# BT_AQ_DOL_R2.net
KiCad netlist of a schematic drawn in EAGLE
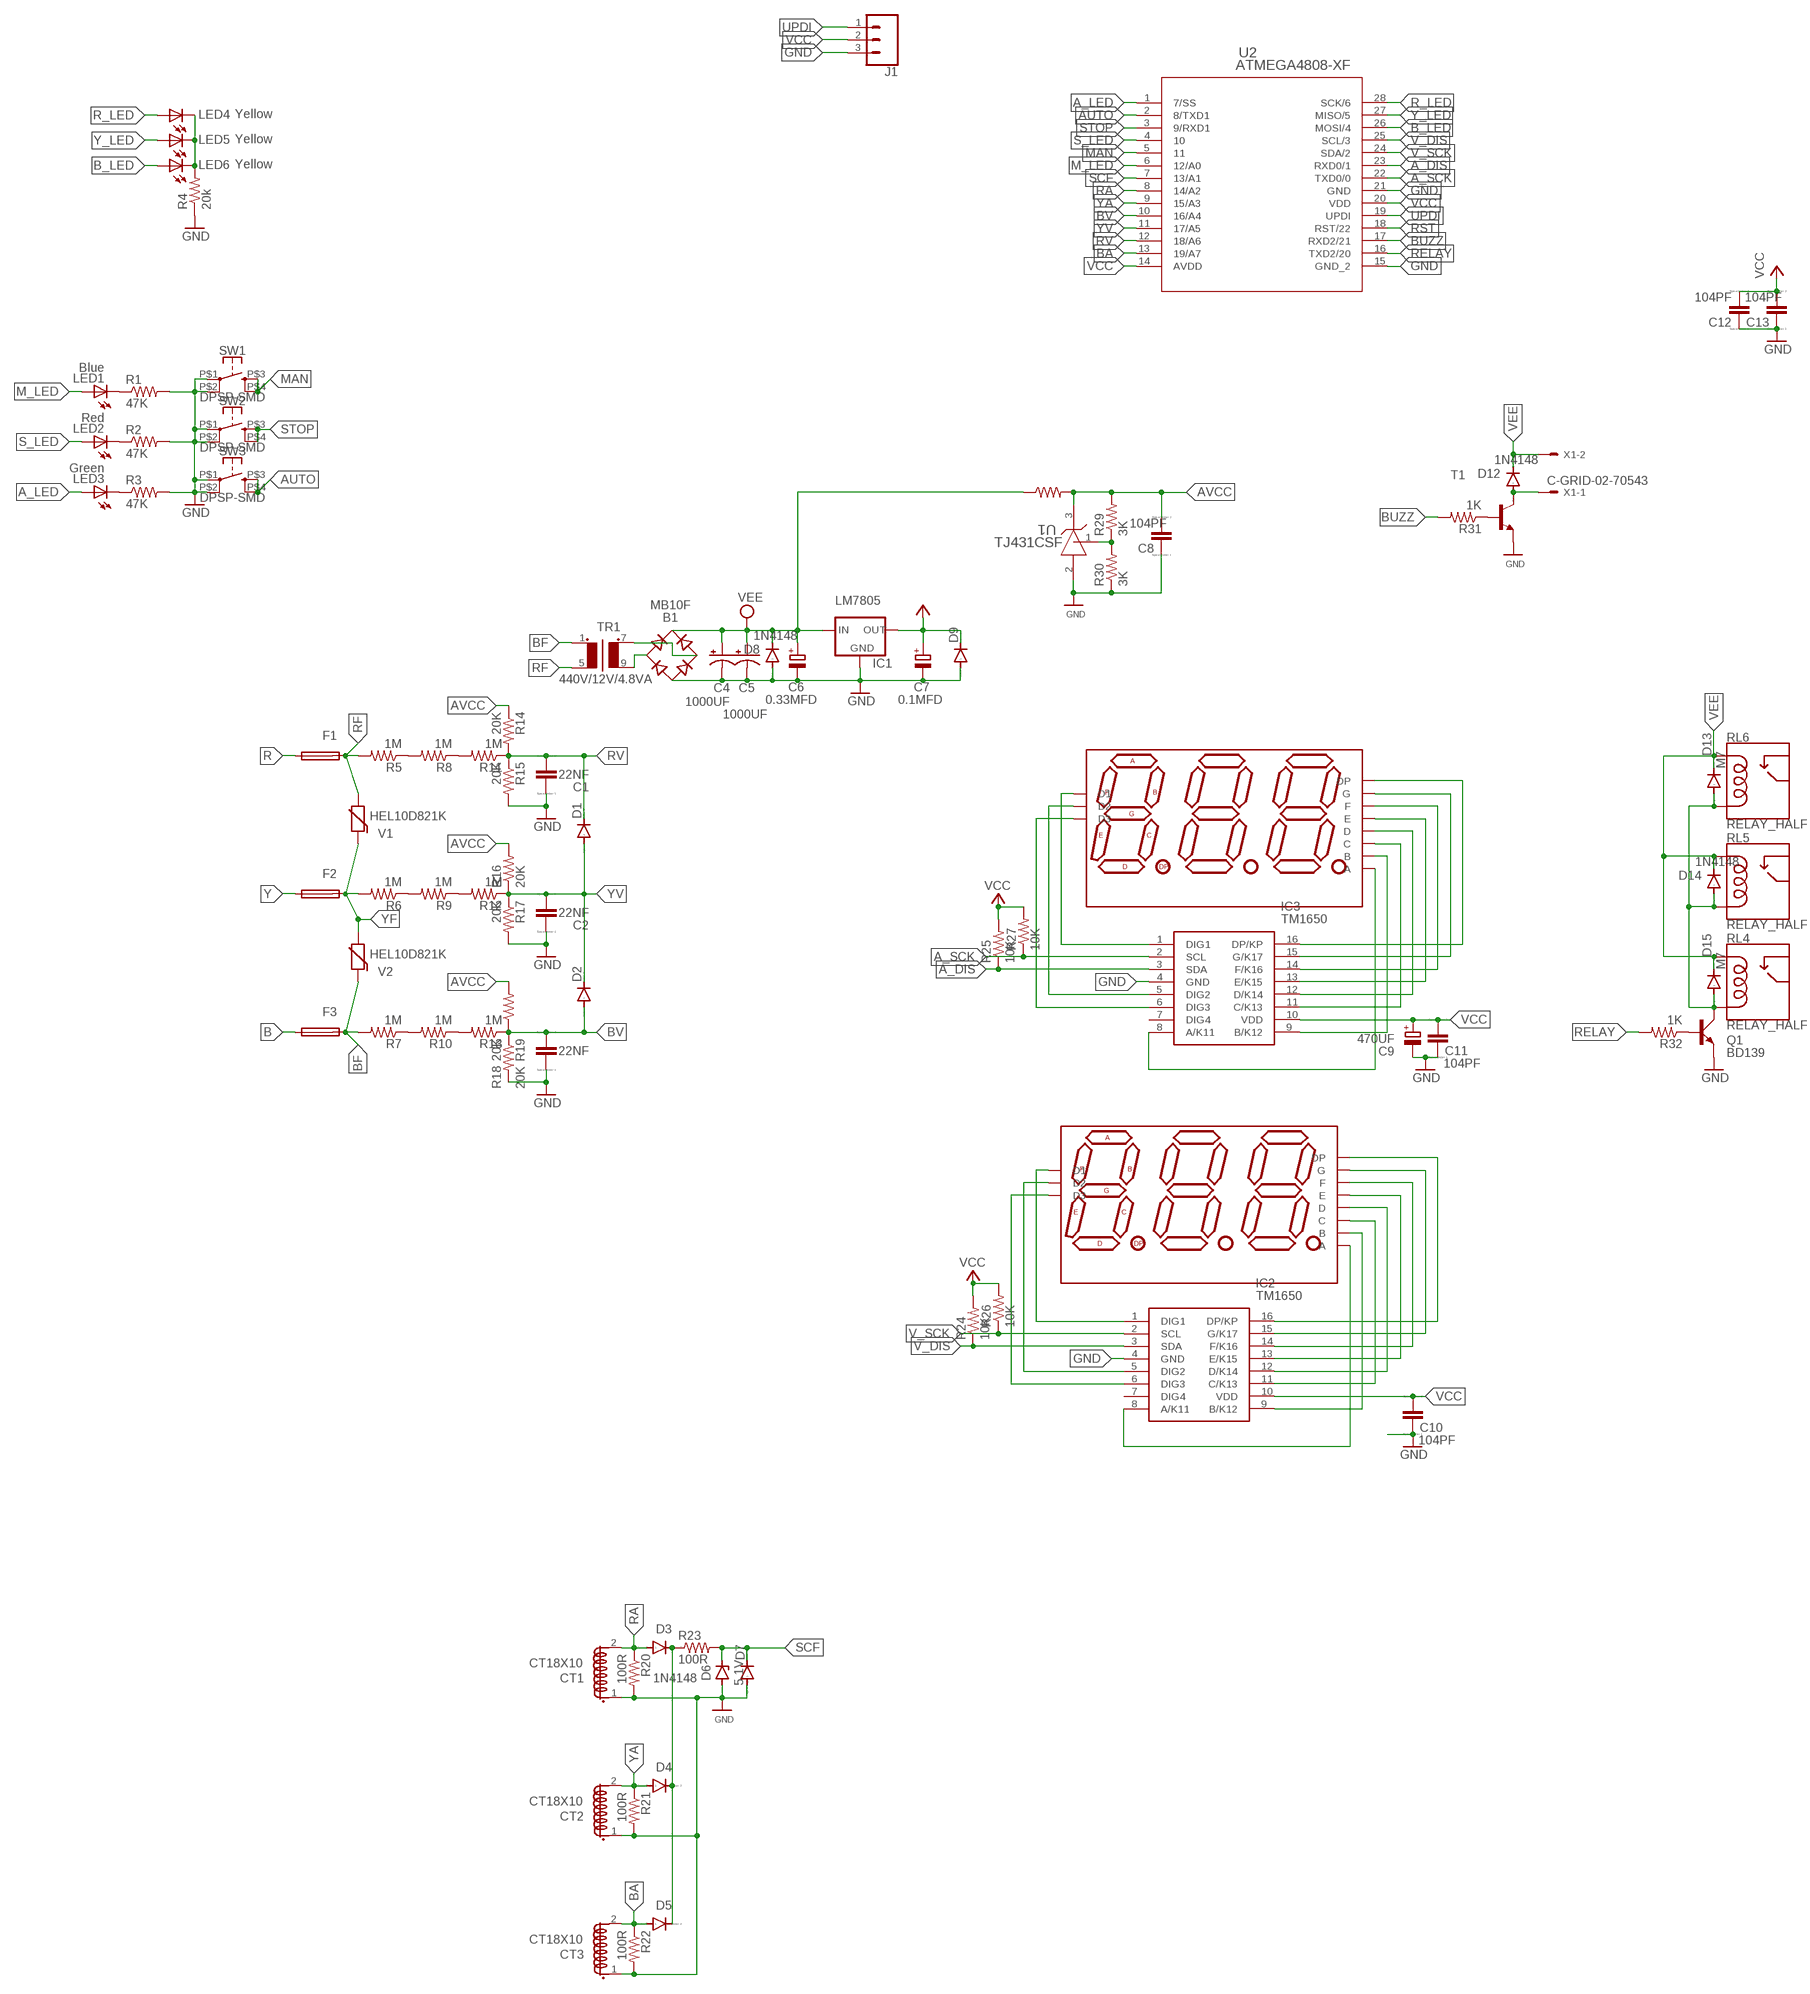
[diagram p0: schematic, sheet 1]

(export (version "E")
  (design (tool "Eeschema 10.0.6"))
  (components
    (comp (ref "B1")
      (value "MB10F")
      (footprint "eagle-import:SOIC-4")
      (libsource (lib "eagle-import") (part "MBS8"))
    )
    (comp (ref "C1")
      (value "22NF")
      (footprint "eagle-import:C1206")
      (libsource (lib "eagle-import") (part "CC1206"))
    )
    (comp (ref "C2")
      (value "22NF")
      (footprint "eagle-import:C1206")
      (libsource (lib "eagle-import") (part "CC1206"))
    )
    (comp (ref "C3")
      (value "22NF")
      (footprint "eagle-import:C1206")
      (libsource (lib "eagle-import") (part "CC1206"))
    )
    (comp (ref "C4")
      (value "1000UF")
      (footprint "eagle-import:E3,5-10")
      (libsource (lib "eagle-import") (part "CPOL-USE3.5-10"))
    )
    (comp (ref "C5")
      (value "1000UF")
      (footprint "eagle-import:E3,5-10")
      (libsource (lib "eagle-import") (part "CPOL-USE3.5-10"))
    )
    (comp (ref "C6")
      (value "0.33MFD")
      (footprint "eagle-import:E2,5-5")
      (libsource (lib "eagle-import") (part "CPOL-EUE2.5-5"))
    )
    (comp (ref "C7")
      (value "0.1MFD")
      (footprint "eagle-import:E2,5-5")
      (libsource (lib "eagle-import") (part "CPOL-EUE2.5-5"))
    )
    (comp (ref "C8")
      (value "104PF")
      (footprint "eagle-import:C1206")
      (libsource (lib "eagle-import") (part "CC1206"))
    )
    (comp (ref "C9")
      (value "470UF")
      (footprint "eagle-import:E3,5-8")
      (libsource (lib "eagle-import") (part "CPOL-EUE3.5-8"))
    )
    (comp (ref "C10")
      (value "104PF")
      (footprint "eagle-import:C1206")
      (libsource (lib "eagle-import") (part "CC1206"))
    )
    (comp (ref "C11")
      (value "104PF")
      (footprint "eagle-import:C1206")
      (libsource (lib "eagle-import") (part "CC1206"))
    )
    (comp (ref "C12")
      (value "104PF")
      (footprint "eagle-import:C1206")
      (libsource (lib "eagle-import") (part "CC1206"))
    )
    (comp (ref "C13")
      (value "104PF")
      (footprint "eagle-import:C1206")
      (libsource (lib "eagle-import") (part "CC1206"))
    )
    (comp (ref "CT1")
      (value "CT18X10")
      (footprint "eagle-import:ZMCT103C")
      (libsource (lib "eagle-import") (part "CT18X10"))
    )
    (comp (ref "CT2")
      (value "CT18X10")
      (footprint "eagle-import:ZMCT103C")
      (libsource (lib "eagle-import") (part "CT18X10"))
    )
    (comp (ref "CT3")
      (value "CT18X10")
      (footprint "eagle-import:ZMCT103C")
      (libsource (lib "eagle-import") (part "CT18X10"))
    )
    (comp (ref "D1")
      (value "DIODE-DO214AA")
      (footprint "eagle-import:DO214AA")
      (libsource (lib "eagle-import") (part "DIODE-DO214AA"))
    )
    (comp (ref "D2")
      (value "DIODE-DO214AA")
      (footprint "eagle-import:DO214AA")
      (libsource (lib "eagle-import") (part "DIODE-DO214AA"))
    )
    (comp (ref "D3")
      (value "1N4148")
      (footprint "eagle-import:MINIMELF")
      (libsource (lib "eagle-import") (part "DIODE-MINIMELF"))
    )
    (comp (ref "D4")
      (value "1N4148")
      (footprint "eagle-import:MINIMELF")
      (libsource (lib "eagle-import") (part "DIODE-MINIMELF"))
    )
    (comp (ref "D5")
      (value "1N4148")
      (footprint "eagle-import:MINIMELF")
      (libsource (lib "eagle-import") (part "DIODE-MINIMELF"))
    )
    (comp (ref "D6")
      (value "5.1V")
      (footprint "eagle-import:DIOMELF3516")
      (libsource (lib "eagle-import") (part "ZENER_DO-213AA(SOD-80)_"))
    )
    (comp (ref "D7")
      (value "DIODE-DO214AA")
      (footprint "eagle-import:DO214AA")
      (libsource (lib "eagle-import") (part "DIODE-DO214AA"))
    )
    (comp (ref "D8")
      (value "1N4148")
      (footprint "eagle-import:MINIMELF")
      (libsource (lib "eagle-import") (part "DIODE-MINIMELF"))
    )
    (comp (ref "D9")
      (value "DIODE-DO214AA")
      (footprint "eagle-import:DO214AA")
      (libsource (lib "eagle-import") (part "DIODE-DO214AA"))
    )
    (comp (ref "D10")
      (value "SUNR036CC3D")
      (footprint "eagle-import:7S3D036_DIP")
      (libsource (lib "eagle-import") (part "7SEGMENT-3DIGITDIP"))
    )
    (comp (ref "D11")
      (value "SUNR036CC3D")
      (footprint "eagle-import:7S3D036_DIP")
      (libsource (lib "eagle-import") (part "7SEGMENT-3DIGITDIP"))
    )
    (comp (ref "D12")
      (value "1N4148")
      (footprint "eagle-import:MINIMELF")
      (libsource (lib "eagle-import") (part "DIODE-MINIMELF"))
    )
    (comp (ref "D13")
      (value "M7")
      (footprint "eagle-import:DO-214AC")
      (libsource (lib "eagle-import") (part "DIODE-DO-214AC"))
    )
    (comp (ref "D14")
      (value "1N4148")
      (footprint "eagle-import:MINIMELF")
      (libsource (lib "eagle-import") (part "DIODE-MINIMELF"))
    )
    (comp (ref "D15")
      (value "M7")
      (footprint "eagle-import:DO-214AC")
      (libsource (lib "eagle-import") (part "DIODE-DO-214AC"))
    )
    (comp (ref "F1")
      (value "TRF600-150")
      (footprint "eagle-import:TRF600-150")
      (libsource (lib "eagle-import") (part "PPTCPTH"))
    )
    (comp (ref "F2")
      (value "TRF600-150")
      (footprint "eagle-import:TRF600-150")
      (libsource (lib "eagle-import") (part "PPTCPTH"))
    )
    (comp (ref "F3")
      (value "TRF600-150")
      (footprint "eagle-import:TRF600-150")
      (libsource (lib "eagle-import") (part "PPTCPTH"))
    )
    (comp (ref "IC1")
      (value "LM7805")
      (footprint "eagle-import:78XXS")
      (libsource (lib "eagle-import") (part "78XXS"))
    )
    (comp (ref "IC2")
      (value "TM1650")
      (footprint "eagle-import:SOIC127P604X185-16N")
      (fields (field (name "MANUFACTURER_PART_NUMBER") "tm1650"))
      (libsource (lib "eagle-import") (part "TM1650"))
    )
    (comp (ref "IC3")
      (value "TM1650")
      (footprint "eagle-import:SOIC127P604X185-16N")
      (fields (field (name "MANUFACTURER_PART_NUMBER") "tm1650"))
      (libsource (lib "eagle-import") (part "TM1650"))
    )
    (comp (ref "J1")
      (value "CONN_03")
      (footprint "eagle-import:1X03")
      (libsource (lib "eagle-import") (part "CONN_03"))
    )
    (comp (ref "LED1")
      (value "Blue")
      (footprint "eagle-import:LED3MM")
      (libsource (lib "eagle-import") (part "LED3MM"))
    )
    (comp (ref "LED2")
      (value "Red")
      (footprint "eagle-import:LED3MM")
      (libsource (lib "eagle-import") (part "LED3MM"))
    )
    (comp (ref "LED3")
      (value "Green")
      (footprint "eagle-import:LED3MM")
      (libsource (lib "eagle-import") (part "LED3MM"))
    )
    (comp (ref "LED4")
      (value "Yellow")
      (footprint "eagle-import:LED3MM")
      (libsource (lib "eagle-import") (part "LED3MM"))
    )
    (comp (ref "LED5")
      (value "Yellow")
      (footprint "eagle-import:LED3MM")
      (libsource (lib "eagle-import") (part "LED3MM"))
    )
    (comp (ref "LED6")
      (value "Yellow")
      (footprint "eagle-import:LED3MM")
      (libsource (lib "eagle-import") (part "LED3MM"))
    )
    (comp (ref "Q1")
      (value "BD139")
      (footprint "eagle-import:TO126AV")
      (libsource (lib "eagle-import") (part "BD139"))
    )
    (comp (ref "R1")
      (value "47K")
      (footprint "eagle-import:M1206")
      (libsource (lib "eagle-import") (part "rcl_334_R-US_M1206"))
    )
    (comp (ref "R2")
      (value "47K")
      (footprint "eagle-import:M1206")
      (libsource (lib "eagle-import") (part "rcl_334_R-US_M1206"))
    )
    (comp (ref "R3")
      (value "47K")
      (footprint "eagle-import:M1206")
      (libsource (lib "eagle-import") (part "rcl_334_R-US_M1206"))
    )
    (comp (ref "R4")
      (value "20k")
      (footprint "eagle-import:M1206")
      (libsource (lib "eagle-import") (part "rcl_334_R-US_M1206"))
    )
    (comp (ref "R5")
      (value "1M")
      (footprint "eagle-import:M1206")
      (libsource (lib "eagle-import") (part "rcl_334_R-US_M1206"))
    )
    (comp (ref "R6")
      (value "1M")
      (footprint "eagle-import:M1206")
      (libsource (lib "eagle-import") (part "rcl_334_R-US_M1206"))
    )
    (comp (ref "R7")
      (value "1M")
      (footprint "eagle-import:M1206")
      (libsource (lib "eagle-import") (part "rcl_334_R-US_M1206"))
    )
    (comp (ref "R8")
      (value "1M")
      (footprint "eagle-import:M1206")
      (libsource (lib "eagle-import") (part "rcl_334_R-US_M1206"))
    )
    (comp (ref "R9")
      (value "1M")
      (footprint "eagle-import:M1206")
      (libsource (lib "eagle-import") (part "rcl_334_R-US_M1206"))
    )
    (comp (ref "R10")
      (value "1M")
      (footprint "eagle-import:M1206")
      (libsource (lib "eagle-import") (part "rcl_334_R-US_M1206"))
    )
    (comp (ref "R11")
      (value "1M")
      (footprint "eagle-import:M1206")
      (libsource (lib "eagle-import") (part "rcl_334_R-US_M1206"))
    )
    (comp (ref "R12")
      (value "1M")
      (footprint "eagle-import:M1206")
      (libsource (lib "eagle-import") (part "rcl_334_R-US_M1206"))
    )
    (comp (ref "R13")
      (value "1M")
      (footprint "eagle-import:M1206")
      (libsource (lib "eagle-import") (part "rcl_334_R-US_M1206"))
    )
    (comp (ref "R14")
      (value "20K")
      (footprint "eagle-import:M1206")
      (libsource (lib "eagle-import") (part "rcl_334_R-US_M1206"))
    )
    (comp (ref "R15")
      (value "20K")
      (footprint "eagle-import:M1206")
      (libsource (lib "eagle-import") (part "rcl_334_R-US_M1206"))
    )
    (comp (ref "R16")
      (value "20K")
      (footprint "eagle-import:M1206")
      (libsource (lib "eagle-import") (part "rcl_334_R-US_M1206"))
    )
    (comp (ref "R17")
      (value "20K")
      (footprint "eagle-import:M1206")
      (libsource (lib "eagle-import") (part "rcl_334_R-US_M1206"))
    )
    (comp (ref "R18")
      (value "20K")
      (footprint "eagle-import:M1206")
      (libsource (lib "eagle-import") (part "rcl_334_R-US_M1206"))
    )
    (comp (ref "R19")
      (value "20K")
      (footprint "eagle-import:M1206")
      (libsource (lib "eagle-import") (part "rcl_334_R-US_M1206"))
    )
    (comp (ref "R20")
      (value "100R")
      (footprint "eagle-import:M1206")
      (libsource (lib "eagle-import") (part "R-US_M1206"))
    )
    (comp (ref "R21")
      (value "100R")
      (footprint "eagle-import:M1206")
      (libsource (lib "eagle-import") (part "R-US_M1206"))
    )
    (comp (ref "R22")
      (value "100R")
      (footprint "eagle-import:M1206")
      (libsource (lib "eagle-import") (part "R-US_M1206"))
    )
    (comp (ref "R23")
      (value "100R")
      (footprint "eagle-import:M1206")
      (libsource (lib "eagle-import") (part "R-US_M1206"))
    )
    (comp (ref "R24")
      (value "10K")
      (footprint "eagle-import:M1206")
      (libsource (lib "eagle-import") (part "rcl_334_R-US_M1206"))
    )
    (comp (ref "R25")
      (value "10K")
      (footprint "eagle-import:M1206")
      (libsource (lib "eagle-import") (part "rcl_334_R-US_M1206"))
    )
    (comp (ref "R26")
      (value "10K")
      (footprint "eagle-import:M1206")
      (libsource (lib "eagle-import") (part "rcl_334_R-US_M1206"))
    )
    (comp (ref "R27")
      (value "10K")
      (footprint "eagle-import:M1206")
      (libsource (lib "eagle-import") (part "rcl_334_R-US_M1206"))
    )
    (comp (ref "R28")
      (value "10K")
      (footprint "eagle-import:M1206")
      (libsource (lib "eagle-import") (part "R-US_M1206"))
    )
    (comp (ref "R29")
      (value "3K")
      (footprint "eagle-import:M1206")
      (libsource (lib "eagle-import") (part "R-US_M1206"))
    )
    (comp (ref "R30")
      (value "3K")
      (footprint "eagle-import:M1206")
      (libsource (lib "eagle-import") (part "R-US_M1206"))
    )
    (comp (ref "R31")
      (value "1K")
      (footprint "eagle-import:M1206")
      (libsource (lib "eagle-import") (part "rcl_334_R-US_M1206"))
    )
    (comp (ref "R32")
      (value "1K")
      (footprint "eagle-import:M1206")
      (libsource (lib "eagle-import") (part "rcl_334_R-US_M1206"))
    )
    (comp (ref "RL4")
      (value "RELAY_HALF")
      (footprint "eagle-import:DT90_HALF")
      (libsource (lib "eagle-import") (part "RELAY_HALF"))
    )
    (comp (ref "RL5")
      (value "RELAY_HALF")
      (footprint "eagle-import:DT90_HALF")
      (libsource (lib "eagle-import") (part "RELAY_HALF"))
    )
    (comp (ref "RL6")
      (value "RELAY_HALF")
      (footprint "eagle-import:DT90_HALF")
      (libsource (lib "eagle-import") (part "RELAY_HALF"))
    )
    (comp (ref "SW1")
      (value "DPSP-SMD")
      (footprint "eagle-import:B3F-40XX-ROUND-SMD")
      (libsource (lib "eagle-import") (part "DPSP-SMD"))
    )
    (comp (ref "SW2")
      (value "DPSP-SMD")
      (footprint "eagle-import:B3F-40XX-ROUND-SMD")
      (libsource (lib "eagle-import") (part "DPSP-SMD"))
    )
    (comp (ref "SW3")
      (value "DPSP-SMD")
      (footprint "eagle-import:B3F-40XX-ROUND-SMD")
      (libsource (lib "eagle-import") (part "DPSP-SMD"))
    )
    (comp (ref "T1")
      (value "MMUN2213LT1-NPN-SC59-BEC")
      (footprint "eagle-import:SC59-BEC")
      (libsource (lib "eagle-import") (part "-NPN-SC59-BECMMUN2213LT1"))
    )
    (comp (ref "TR1")
      (value "440V/12V/4.8VA")
      (footprint "eagle-import:440V12V6VA")
      (libsource (lib "eagle-import") (part "TRANSFORMER6VA"))
    )
    (comp (ref "U1")
      (value "TJ431CSF")
      (footprint "eagle-import:SOT-23")
      (fields
        (field (name "MANUFACTURER_PART_NUMBER") "TL431IDBZTG4")
        (field (name "COPYRIGHT") "Copyright (C) 2022 Ultra Librarian. All rights reserved.")
      )
      (libsource (lib "eagle-import") (part "TJ431CSFDBZ0003A_L"))
    )
    (comp (ref "U2")
      (value "ATMEGA4808-XF")
      (footprint "eagle-import:SSOP28_SS_MCH")
      (fields (field (name "COPYRIGHT") "Copyright (C) 2022 Ultra Librarian. All rights reserved."))
      (libsource (lib "eagle-import") (part "ATMEGA4808-XF"))
    )
    (comp (ref "V1")
      (value "HEL10D821K")
      (footprint "eagle-import:10MM")
      (libsource (lib "eagle-import") (part "VARISTOR"))
    )
    (comp (ref "V2")
      (value "HEL10D821K")
      (footprint "eagle-import:10MM")
      (libsource (lib "eagle-import") (part "VARISTOR"))
    )
    (comp (ref "X1")
      (value "C-GRID-02-70543")
      (footprint "eagle-import:70543-02")
      (fields (field (name "MF") "MOLEX"))
      (libsource (lib "eagle-import") (part "C-GRID-02-70543"))
    )
  )
  (nets
    (net (code "1") (name "AUTO") (class "Default")
      (node (ref "SW3") (pin "P$3") (pinfunction "3_P$3") (pintype "passive"))
      (node (ref "SW3") (pin "P$4") (pinfunction "4_P$4") (pintype "passive"))
      (node (ref "U2") (pin "2") (pinfunction "8/TXD1_2") (pintype "bidirectional"))
    )
    (net (code "2") (name "AVCC") (class "Default")
      (node (ref "C8") (pin "2") (pinfunction "2_2") (pintype "passive"))
      (node (ref "R14") (pin "1") (pinfunction "1_1") (pintype "passive"))
      (node (ref "R16") (pin "2") (pinfunction "2_2") (pintype "passive"))
      (node (ref "R18") (pin "2") (pinfunction "2_2") (pintype "passive"))
      (node (ref "R28") (pin "2") (pinfunction "2_2") (pintype "passive"))
      (node (ref "R29") (pin "2") (pinfunction "2_2") (pintype "passive"))
      (node (ref "U1") (pin "3") (pinfunction "CATHODE_3") (pintype "passive"))
    )
    (net (code "3") (name "A_DIS") (class "Default")
      (node (ref "IC3") (pin "3") (pinfunction "SDA_3") (pintype "input"))
      (node (ref "R25") (pin "1") (pinfunction "1_1") (pintype "passive"))
      (node (ref "U2") (pin "23") (pinfunction "RXD0/1_23") (pintype "bidirectional"))
    )
    (net (code "4") (name "A_LED") (class "Default")
      (node (ref "LED3") (pin "A") (pinfunction "A_A") (pintype "passive"))
      (node (ref "U2") (pin "1") (pinfunction "7/SS_1") (pintype "bidirectional"))
    )
    (net (code "5") (name "A_SCK") (class "Default")
      (node (ref "IC3") (pin "2") (pinfunction "SCL_2") (pintype "input"))
      (node (ref "R27") (pin "1") (pinfunction "1_1") (pintype "passive"))
      (node (ref "U2") (pin "22") (pinfunction "TXD0/0_22") (pintype "bidirectional"))
    )
    (net (code "6") (name "B") (class "Default")
      (node (ref "F3") (pin "1") (pinfunction "1_1") (pintype "passive"))
    )
    (net (code "7") (name "BA") (class "Default")
      (node (ref "CT3") (pin "2") (pinfunction "S1.2_2") (pintype "passive"))
      (node (ref "D5") (pin "A") (pinfunction "A_A") (pintype "passive"))
      (node (ref "R22") (pin "1") (pinfunction "1_1") (pintype "passive"))
      (node (ref "U2") (pin "13") (pinfunction "19/A7_13") (pintype "bidirectional"))
    )
    (net (code "8") (name "BF") (class "Default")
      (node (ref "F3") (pin "2") (pinfunction "2_2") (pintype "passive"))
      (node (ref "R7") (pin "2") (pinfunction "2_2") (pintype "passive"))
      (node (ref "TR1") (pin "1") (pinfunction "P1_1") (pintype "passive"))
      (node (ref "V2") (pin "1") (pinfunction "1_1") (pintype "passive"))
    )
    (net (code "9") (name "BUZZ") (class "Default")
      (node (ref "R31") (pin "2") (pinfunction "2_2") (pintype "passive"))
      (node (ref "U2") (pin "17") (pinfunction "RXD2/21_17") (pintype "bidirectional"))
    )
    (net (code "10") (name "BV") (class "Default")
      (node (ref "C3") (pin "2") (pinfunction "2_2") (pintype "passive"))
      (node (ref "D2") (pin "A") (pinfunction "A_A") (pintype "passive"))
      (node (ref "R13") (pin "1") (pinfunction "1_1") (pintype "passive"))
      (node (ref "R18") (pin "1") (pinfunction "1_1") (pintype "passive"))
      (node (ref "R19") (pin "1") (pinfunction "1_1") (pintype "passive"))
      (node (ref "U2") (pin "10") (pinfunction "16/A4_10") (pintype "bidirectional"))
    )
    (net (code "11") (name "B_LED") (class "Default")
      (node (ref "LED6") (pin "A") (pinfunction "A_A") (pintype "passive"))
      (node (ref "U2") (pin "26") (pinfunction "MOSI/4_26") (pintype "bidirectional"))
    )
    (net (code "12") (name "GND") (class "Default")
      (node (ref "B1") (pin "-") (pinfunction "-_-") (pintype "passive"))
      (node (ref "C1") (pin "1") (pinfunction "1_1") (pintype "passive"))
      (node (ref "C10") (pin "1") (pinfunction "1_1") (pintype "passive"))
      (node (ref "C11") (pin "1") (pinfunction "1_1") (pintype "passive"))
      (node (ref "C12") (pin "1") (pinfunction "1_1") (pintype "passive"))
      (node (ref "C13") (pin "1") (pinfunction "1_1") (pintype "passive"))
      (node (ref "C2") (pin "1") (pinfunction "1_1") (pintype "passive"))
      (node (ref "C3") (pin "1") (pinfunction "1_1") (pintype "passive"))
      (node (ref "C4") (pin "-") (pinfunction "-_-") (pintype "passive"))
      (node (ref "C5") (pin "-") (pinfunction "-_-") (pintype "passive"))
      (node (ref "C6") (pin "-") (pinfunction "-_-") (pintype "passive"))
      (node (ref "C7") (pin "-") (pinfunction "-_-") (pintype "passive"))
      (node (ref "C8") (pin "1") (pinfunction "1_1") (pintype "passive"))
      (node (ref "C9") (pin "-") (pinfunction "-_-") (pintype "passive"))
      (node (ref "CT1") (pin "1") (pinfunction "S1.1_1") (pintype "passive"))
      (node (ref "CT2") (pin "1") (pinfunction "S1.1_1") (pintype "passive"))
      (node (ref "CT3") (pin "1") (pinfunction "S1.1_1") (pintype "passive"))
      (node (ref "D6") (pin "2") (pinfunction "A_2") (pintype "passive"))
      (node (ref "D7") (pin "A") (pinfunction "A_A") (pintype "passive"))
      (node (ref "D8") (pin "A") (pinfunction "A_A") (pintype "passive"))
      (node (ref "D9") (pin "A") (pinfunction "A_A") (pintype "passive"))
      (node (ref "IC1") (pin "GND") (pinfunction "GND_GND") (pintype "input"))
      (node (ref "IC2") (pin "4") (pinfunction "GND_4") (pintype "power_in"))
      (node (ref "IC3") (pin "4") (pinfunction "GND_4") (pintype "power_in"))
      (node (ref "J1") (pin "3") (pinfunction "3_3") (pintype "passive"))
      (node (ref "Q1") (pin "E") (pinfunction "E_E") (pintype "passive"))
      (node (ref "R1") (pin "2") (pinfunction "2_2") (pintype "passive"))
      (node (ref "R15") (pin "2") (pinfunction "2_2") (pintype "passive"))
      (node (ref "R17") (pin "2") (pinfunction "2_2") (pintype "passive"))
      (node (ref "R19") (pin "2") (pinfunction "2_2") (pintype "passive"))
      (node (ref "R2") (pin "2") (pinfunction "2_2") (pintype "passive"))
      (node (ref "R20") (pin "2") (pinfunction "2_2") (pintype "passive"))
      (node (ref "R21") (pin "2") (pinfunction "2_2") (pintype "passive"))
      (node (ref "R22") (pin "2") (pinfunction "2_2") (pintype "passive"))
      (node (ref "R3") (pin "2") (pinfunction "2_2") (pintype "passive"))
      (node (ref "R30") (pin "1") (pinfunction "1_1") (pintype "passive"))
      (node (ref "R4") (pin "1") (pinfunction "1_1") (pintype "passive"))
      (node (ref "SW1") (pin "P$1") (pinfunction "1_P$1") (pintype "passive"))
      (node (ref "SW1") (pin "P$2") (pinfunction "2_P$2") (pintype "passive"))
      (node (ref "SW2") (pin "P$1") (pinfunction "1_P$1") (pintype "passive"))
      (node (ref "SW2") (pin "P$2") (pinfunction "2_P$2") (pintype "passive"))
      (node (ref "SW3") (pin "P$1") (pinfunction "1_P$1") (pintype "passive"))
      (node (ref "SW3") (pin "P$2") (pinfunction "2_P$2") (pintype "passive"))
      (node (ref "T1") (pin "E") (pinfunction "E_E") (pintype "passive"))
      (node (ref "U1") (pin "2") (pinfunction "ANODE_2") (pintype "passive"))
      (node (ref "U2") (pin "15") (pinfunction "GND_2_15") (pintype "passive"))
      (node (ref "U2") (pin "21") (pinfunction "GND_21") (pintype "passive"))
    )
    (net (code "13") (name "MAN") (class "Default")
      (node (ref "SW1") (pin "P$3") (pinfunction "3_P$3") (pintype "passive"))
      (node (ref "SW1") (pin "P$4") (pinfunction "4_P$4") (pintype "passive"))
      (node (ref "U2") (pin "5") (pinfunction "11_5") (pintype "bidirectional"))
    )
    (net (code "14") (name "M_LED") (class "Default")
      (node (ref "LED1") (pin "A") (pinfunction "A_A") (pintype "passive"))
      (node (ref "U2") (pin "6") (pinfunction "12/A0_6") (pintype "bidirectional"))
    )
    (net (code "15") (name "Net-(B1-AC1)") (class "Default")
      (node (ref "B1") (pin "~1") (pinfunction "AC1_~1") (pintype "passive"))
      (node (ref "TR1") (pin "9") (pinfunction "S2_9") (pintype "passive"))
    )
    (net (code "16") (name "Net-(B1-AC2)") (class "Default")
      (node (ref "B1") (pin "~2") (pinfunction "AC2_~2") (pintype "passive"))
      (node (ref "TR1") (pin "7") (pinfunction "S1_7") (pintype "passive"))
    )
    (net (code "17") (name "Net-(D3-PadC)") (class "Default")
      (node (ref "D3") (pin "C") (pinfunction "C_C") (pintype "passive"))
      (node (ref "D4") (pin "C") (pinfunction "C_C") (pintype "passive"))
      (node (ref "D5") (pin "C") (pinfunction "C_C") (pintype "passive"))
      (node (ref "R23") (pin "1") (pinfunction "1_1") (pintype "passive"))
    )
    (net (code "18") (name "Net-(D10-A)") (class "Default")
      (node (ref "D10") (pin "11") (pinfunction "A_11") (pintype "bidirectional"))
      (node (ref "IC2") (pin "8") (pinfunction "A/K11_8") (pintype "bidirectional"))
    )
    (net (code "19") (name "Net-(D10-B)") (class "Default")
      (node (ref "D10") (pin "7") (pinfunction "B_7") (pintype "bidirectional"))
      (node (ref "IC2") (pin "9") (pinfunction "B/K12_9") (pintype "bidirectional"))
    )
    (net (code "20") (name "Net-(D10-C)") (class "Default")
      (node (ref "D10") (pin "4") (pinfunction "C_4") (pintype "bidirectional"))
      (node (ref "IC2") (pin "11") (pinfunction "C/K13_11") (pintype "bidirectional"))
    )
    (net (code "21") (name "Net-(D10-D)") (class "Default")
      (node (ref "D10") (pin "2") (pinfunction "D_2") (pintype "bidirectional"))
      (node (ref "IC2") (pin "12") (pinfunction "D/K14_12") (pintype "bidirectional"))
    )
    (net (code "22") (name "Net-(D10-D1)") (class "Default")
      (node (ref "D10") (pin "12") (pinfunction "D1_12") (pintype "bidirectional"))
      (node (ref "IC2") (pin "1") (pinfunction "DIG1_1") (pintype "bidirectional"))
    )
    (net (code "23") (name "Net-(D10-D2)") (class "Default")
      (node (ref "D10") (pin "9") (pinfunction "D2_9") (pintype "bidirectional"))
      (node (ref "IC2") (pin "5") (pinfunction "DIG2_5") (pintype "bidirectional"))
    )
    (net (code "24") (name "Net-(D10-D3)") (class "Default")
      (node (ref "D10") (pin "8") (pinfunction "D3_8") (pintype "bidirectional"))
      (node (ref "IC2") (pin "6") (pinfunction "DIG3_6") (pintype "bidirectional"))
    )
    (net (code "25") (name "Net-(D10-DP)") (class "Default")
      (node (ref "D10") (pin "3") (pinfunction "DP_3") (pintype "bidirectional"))
      (node (ref "IC2") (pin "16") (pinfunction "DP/KP_16") (pintype "bidirectional"))
    )
    (net (code "26") (name "Net-(D10-E)") (class "Default")
      (node (ref "D10") (pin "1") (pinfunction "E_1") (pintype "bidirectional"))
      (node (ref "IC2") (pin "13") (pinfunction "E/K15_13") (pintype "bidirectional"))
    )
    (net (code "27") (name "Net-(D10-F)") (class "Default")
      (node (ref "D10") (pin "10") (pinfunction "F_10") (pintype "bidirectional"))
      (node (ref "IC2") (pin "14") (pinfunction "F/K16_14") (pintype "bidirectional"))
    )
    (net (code "28") (name "Net-(D10-G)") (class "Default")
      (node (ref "D10") (pin "5") (pinfunction "G_5") (pintype "bidirectional"))
      (node (ref "IC2") (pin "15") (pinfunction "G/K17_15") (pintype "bidirectional"))
    )
    (net (code "29") (name "Net-(D11-A)") (class "Default")
      (node (ref "D11") (pin "11") (pinfunction "A_11") (pintype "bidirectional"))
      (node (ref "IC3") (pin "8") (pinfunction "A/K11_8") (pintype "bidirectional"))
    )
    (net (code "30") (name "Net-(D11-B)") (class "Default")
      (node (ref "D11") (pin "7") (pinfunction "B_7") (pintype "bidirectional"))
      (node (ref "IC3") (pin "9") (pinfunction "B/K12_9") (pintype "bidirectional"))
    )
    (net (code "31") (name "Net-(D11-C)") (class "Default")
      (node (ref "D11") (pin "4") (pinfunction "C_4") (pintype "bidirectional"))
      (node (ref "IC3") (pin "11") (pinfunction "C/K13_11") (pintype "bidirectional"))
    )
    (net (code "32") (name "Net-(D11-D)") (class "Default")
      (node (ref "D11") (pin "2") (pinfunction "D_2") (pintype "bidirectional"))
      (node (ref "IC3") (pin "12") (pinfunction "D/K14_12") (pintype "bidirectional"))
    )
    (net (code "33") (name "Net-(D11-D1)") (class "Default")
      (node (ref "D11") (pin "12") (pinfunction "D1_12") (pintype "bidirectional"))
      (node (ref "IC3") (pin "1") (pinfunction "DIG1_1") (pintype "bidirectional"))
    )
    (net (code "34") (name "Net-(D11-D2)") (class "Default")
      (node (ref "D11") (pin "9") (pinfunction "D2_9") (pintype "bidirectional"))
      (node (ref "IC3") (pin "5") (pinfunction "DIG2_5") (pintype "bidirectional"))
    )
    (net (code "35") (name "Net-(D11-D3)") (class "Default")
      (node (ref "D11") (pin "8") (pinfunction "D3_8") (pintype "bidirectional"))
      (node (ref "IC3") (pin "6") (pinfunction "DIG3_6") (pintype "bidirectional"))
    )
    (net (code "36") (name "Net-(D11-DP)") (class "Default")
      (node (ref "D11") (pin "3") (pinfunction "DP_3") (pintype "bidirectional"))
      (node (ref "IC3") (pin "16") (pinfunction "DP/KP_16") (pintype "bidirectional"))
    )
    (net (code "37") (name "Net-(D11-E)") (class "Default")
      (node (ref "D11") (pin "1") (pinfunction "E_1") (pintype "bidirectional"))
      (node (ref "IC3") (pin "13") (pinfunction "E/K15_13") (pintype "bidirectional"))
    )
    (net (code "38") (name "Net-(D11-F)") (class "Default")
      (node (ref "D11") (pin "10") (pinfunction "F_10") (pintype "bidirectional"))
      (node (ref "IC3") (pin "14") (pinfunction "F/K16_14") (pintype "bidirectional"))
    )
    (net (code "39") (name "Net-(D11-G)") (class "Default")
      (node (ref "D11") (pin "5") (pinfunction "G_5") (pintype "bidirectional"))
      (node (ref "IC3") (pin "15") (pinfunction "G/K17_15") (pintype "bidirectional"))
    )
    (net (code "40") (name "Net-(LED1-C)") (class "Default")
      (node (ref "LED1") (pin "K") (pinfunction "C_K") (pintype "passive"))
      (node (ref "R1") (pin "1") (pinfunction "1_1") (pintype "passive"))
    )
    (net (code "41") (name "Net-(LED2-C)") (class "Default")
      (node (ref "LED2") (pin "K") (pinfunction "C_K") (pintype "passive"))
      (node (ref "R2") (pin "1") (pinfunction "1_1") (pintype "passive"))
    )
    (net (code "42") (name "Net-(LED3-C)") (class "Default")
      (node (ref "LED3") (pin "K") (pinfunction "C_K") (pintype "passive"))
      (node (ref "R3") (pin "1") (pinfunction "1_1") (pintype "passive"))
    )
    (net (code "43") (name "Net-(LED4-C)") (class "Default")
      (node (ref "LED4") (pin "K") (pinfunction "C_K") (pintype "passive"))
      (node (ref "LED5") (pin "K") (pinfunction "C_K") (pintype "passive"))
      (node (ref "LED6") (pin "K") (pinfunction "C_K") (pintype "passive"))
      (node (ref "R4") (pin "2") (pinfunction "2_2") (pintype "passive"))
    )
    (net (code "44") (name "Net-(Q1-PadB)") (class "Default")
      (node (ref "Q1") (pin "B") (pinfunction "B_B") (pintype "passive"))
      (node (ref "R32") (pin "1") (pinfunction "1_1") (pintype "passive"))
    )
    (net (code "45") (name "Net-(R5-Pad1)") (class "Default")
      (node (ref "R5") (pin "1") (pinfunction "1_1") (pintype "passive"))
      (node (ref "R8") (pin "2") (pinfunction "2_2") (pintype "passive"))
    )
    (net (code "46") (name "Net-(R6-Pad1)") (class "Default")
      (node (ref "R6") (pin "1") (pinfunction "1_1") (pintype "passive"))
      (node (ref "R9") (pin "2") (pinfunction "2_2") (pintype "passive"))
    )
    (net (code "47") (name "Net-(R10-Pad1)") (class "Default")
      (node (ref "R10") (pin "1") (pinfunction "1_1") (pintype "passive"))
      (node (ref "R13") (pin "2") (pinfunction "2_2") (pintype "passive"))
    )
    (net (code "48") (name "Net-(R10-Pad2)") (class "Default")
      (node (ref "R10") (pin "2") (pinfunction "2_2") (pintype "passive"))
      (node (ref "R7") (pin "1") (pinfunction "1_1") (pintype "passive"))
    )
    (net (code "49") (name "Net-(R11-Pad2)") (class "Default")
      (node (ref "R11") (pin "2") (pinfunction "2_2") (pintype "passive"))
      (node (ref "R8") (pin "1") (pinfunction "1_1") (pintype "passive"))
    )
    (net (code "50") (name "Net-(R12-Pad2)") (class "Default")
      (node (ref "R12") (pin "2") (pinfunction "2_2") (pintype "passive"))
      (node (ref "R9") (pin "1") (pinfunction "1_1") (pintype "passive"))
    )
    (net (code "51") (name "Net-(R31-Pad1)") (class "Default")
      (node (ref "R31") (pin "1") (pinfunction "1_1") (pintype "passive"))
      (node (ref "T1") (pin "B") (pinfunction "B_B") (pintype "passive"))
    )
    (net (code "52") (name "Net-(RL4-COIL2)") (class "Default")
      (node (ref "D13") (pin "A") (pinfunction "A_A") (pintype "passive"))
      (node (ref "D14") (pin "A") (pinfunction "A_A") (pintype "passive"))
      (node (ref "D15") (pin "A") (pinfunction "A_A") (pintype "passive"))
      (node (ref "Q1") (pin "C") (pinfunction "C_C") (pintype "passive"))
      (node (ref "RL4") (pin "2") (pinfunction "COIL2_2") (pintype "bidirectional"))
      (node (ref "RL5") (pin "2") (pinfunction "COIL2_2") (pintype "bidirectional"))
      (node (ref "RL6") (pin "2") (pinfunction "COIL2_2") (pintype "bidirectional"))
    )
    (net (code "53") (name "Net-(U1-REF)") (class "Default")
      (node (ref "R29") (pin "1") (pinfunction "1_1") (pintype "passive"))
      (node (ref "R30") (pin "2") (pinfunction "2_2") (pintype "passive"))
      (node (ref "U1") (pin "1") (pinfunction "REF_1") (pintype "input"))
    )
    (net (code "54") (name "Net-(X1A-S)") (class "Default")
      (node (ref "D12") (pin "A") (pinfunction "A_A") (pintype "passive"))
      (node (ref "T1") (pin "C") (pinfunction "C_C") (pintype "passive"))
      (node (ref "X1") (pin "1") (pinfunction "S_1") (pintype "passive"))
    )
    (net (code "55") (name "R") (class "Default")
      (node (ref "F1") (pin "1") (pinfunction "1_1") (pintype "passive"))
    )
    (net (code "56") (name "RA") (class "Default")
      (node (ref "CT1") (pin "2") (pinfunction "S1.2_2") (pintype "passive"))
      (node (ref "D3") (pin "A") (pinfunction "A_A") (pintype "passive"))
      (node (ref "R20") (pin "1") (pinfunction "1_1") (pintype "passive"))
      (node (ref "U2") (pin "8") (pinfunction "14/A2_8") (pintype "bidirectional"))
    )
    (net (code "57") (name "RELAY") (class "Default")
      (node (ref "R32") (pin "2") (pinfunction "2_2") (pintype "passive"))
      (node (ref "U2") (pin "16") (pinfunction "TXD2/20_16") (pintype "bidirectional"))
    )
    (net (code "58") (name "RF") (class "Default")
      (node (ref "F1") (pin "2") (pinfunction "2_2") (pintype "passive"))
      (node (ref "R5") (pin "2") (pinfunction "2_2") (pintype "passive"))
      (node (ref "TR1") (pin "5") (pinfunction "P2_5") (pintype "passive"))
      (node (ref "V1") (pin "2") (pinfunction "2_2") (pintype "passive"))
    )
    (net (code "59") (name "RST") (class "Default")
      (node (ref "U2") (pin "18") (pinfunction "RST/22_18") (pintype "bidirectional"))
    )
    (net (code "60") (name "RV") (class "Default")
      (node (ref "C1") (pin "2") (pinfunction "2_2") (pintype "passive"))
      (node (ref "D1") (pin "C") (pinfunction "C_C") (pintype "passive"))
      (node (ref "R11") (pin "1") (pinfunction "1_1") (pintype "passive"))
      (node (ref "R14") (pin "2") (pinfunction "2_2") (pintype "passive"))
      (node (ref "R15") (pin "1") (pinfunction "1_1") (pintype "passive"))
      (node (ref "U2") (pin "12") (pinfunction "18/A6_12") (pintype "bidirectional"))
    )
    (net (code "61") (name "R_LED") (class "Default")
      (node (ref "LED4") (pin "A") (pinfunction "A_A") (pintype "passive"))
      (node (ref "U2") (pin "28") (pinfunction "SCK/6_28") (pintype "bidirectional"))
    )
    (net (code "62") (name "SCF") (class "Default")
      (node (ref "D6") (pin "1") (pinfunction "C_1") (pintype "passive"))
      (node (ref "D7") (pin "C") (pinfunction "C_C") (pintype "passive"))
      (node (ref "R23") (pin "2") (pinfunction "2_2") (pintype "passive"))
      (node (ref "U2") (pin "7") (pinfunction "13/A1_7") (pintype "bidirectional"))
    )
    (net (code "63") (name "STOP") (class "Default")
      (node (ref "SW2") (pin "P$3") (pinfunction "3_P$3") (pintype "passive"))
      (node (ref "SW2") (pin "P$4") (pinfunction "4_P$4") (pintype "passive"))
      (node (ref "U2") (pin "3") (pinfunction "9/RXD1_3") (pintype "bidirectional"))
    )
    (net (code "64") (name "S_LED") (class "Default")
      (node (ref "LED2") (pin "A") (pinfunction "A_A") (pintype "passive"))
      (node (ref "U2") (pin "4") (pinfunction "10_4") (pintype "bidirectional"))
    )
    (net (code "65") (name "UPDI") (class "Default")
      (node (ref "J1") (pin "1") (pinfunction "1_1") (pintype "passive"))
      (node (ref "U2") (pin "19") (pinfunction "UPDI_19") (pintype "bidirectional"))
    )
    (net (code "66") (name "VCC") (class "Default")
      (node (ref "C10") (pin "2") (pinfunction "2_2") (pintype "passive"))
      (node (ref "C11") (pin "2") (pinfunction "2_2") (pintype "passive"))
      (node (ref "C12") (pin "2") (pinfunction "2_2") (pintype "passive"))
      (node (ref "C13") (pin "2") (pinfunction "2_2") (pintype "passive"))
      (node (ref "C7") (pin "+") (pinfunction "+_+") (pintype "passive"))
      (node (ref "C9") (pin "+") (pinfunction "+_+") (pintype "passive"))
      (node (ref "D9") (pin "C") (pinfunction "C_C") (pintype "passive"))
      (node (ref "IC1") (pin "OUT") (pinfunction "OUT_OUT") (pintype "passive"))
      (node (ref "IC2") (pin "10") (pinfunction "VDD_10") (pintype "power_in"))
      (node (ref "IC3") (pin "10") (pinfunction "VDD_10") (pintype "power_in"))
      (node (ref "J1") (pin "2") (pinfunction "2_2") (pintype "passive"))
      (node (ref "R24") (pin "2") (pinfunction "2_2") (pintype "passive"))
      (node (ref "R25") (pin "2") (pinfunction "2_2") (pintype "passive"))
      (node (ref "R26") (pin "2") (pinfunction "2_2") (pintype "passive"))
      (node (ref "R27") (pin "2") (pinfunction "2_2") (pintype "passive"))
      (node (ref "U2") (pin "14") (pinfunction "AVDD_14") (pintype "power_in"))
      (node (ref "U2") (pin "20") (pinfunction "VDD_20") (pintype "power_in"))
    )
    (net (code "67") (name "VEE") (class "Default")
      (node (ref "B1") (pin "+") (pinfunction "+_+") (pintype "passive"))
      (node (ref "C4") (pin "+") (pinfunction "+_+") (pintype "passive"))
      (node (ref "C5") (pin "+") (pinfunction "+_+") (pintype "passive"))
      (node (ref "C6") (pin "+") (pinfunction "+_+") (pintype "passive"))
      (node (ref "D12") (pin "C") (pinfunction "C_C") (pintype "passive"))
      (node (ref "D13") (pin "C") (pinfunction "C_C") (pintype "passive"))
      (node (ref "D14") (pin "C") (pinfunction "C_C") (pintype "passive"))
      (node (ref "D15") (pin "C") (pinfunction "C_C") (pintype "passive"))
      (node (ref "D8") (pin "C") (pinfunction "C_C") (pintype "passive"))
      (node (ref "IC1") (pin "IN") (pinfunction "IN_IN") (pintype "input"))
      (node (ref "R28") (pin "1") (pinfunction "1_1") (pintype "passive"))
      (node (ref "RL4") (pin "1") (pinfunction "COIL1_1") (pintype "bidirectional"))
      (node (ref "RL5") (pin "1") (pinfunction "COIL1_1") (pintype "bidirectional"))
      (node (ref "RL6") (pin "1") (pinfunction "COIL1_1") (pintype "bidirectional"))
      (node (ref "X1") (pin "2") (pinfunction "S_2") (pintype "passive"))
    )
    (net (code "68") (name "V_DIS") (class "Default")
      (node (ref "IC2") (pin "3") (pinfunction "SDA_3") (pintype "input"))
      (node (ref "R24") (pin "1") (pinfunction "1_1") (pintype "passive"))
      (node (ref "U2") (pin "25") (pinfunction "SCL/3_25") (pintype "bidirectional"))
    )
    (net (code "69") (name "V_SCK") (class "Default")
      (node (ref "IC2") (pin "2") (pinfunction "SCL_2") (pintype "input"))
      (node (ref "R26") (pin "1") (pinfunction "1_1") (pintype "passive"))
      (node (ref "U2") (pin "24") (pinfunction "SDA/2_24") (pintype "bidirectional"))
    )
    (net (code "70") (name "Y") (class "Default")
      (node (ref "F2") (pin "1") (pinfunction "1_1") (pintype "passive"))
    )
    (net (code "71") (name "YA") (class "Default")
      (node (ref "CT2") (pin "2") (pinfunction "S1.2_2") (pintype "passive"))
      (node (ref "D4") (pin "A") (pinfunction "A_A") (pintype "passive"))
      (node (ref "R21") (pin "1") (pinfunction "1_1") (pintype "passive"))
      (node (ref "U2") (pin "9") (pinfunction "15/A3_9") (pintype "bidirectional"))
    )
    (net (code "72") (name "YF") (class "Default")
      (node (ref "F2") (pin "2") (pinfunction "2_2") (pintype "passive"))
      (node (ref "R6") (pin "2") (pinfunction "2_2") (pintype "passive"))
      (node (ref "V1") (pin "1") (pinfunction "1_1") (pintype "passive"))
      (node (ref "V2") (pin "2") (pinfunction "2_2") (pintype "passive"))
    )
    (net (code "73") (name "YV") (class "Default")
      (node (ref "C2") (pin "2") (pinfunction "2_2") (pintype "passive"))
      (node (ref "D1") (pin "A") (pinfunction "A_A") (pintype "passive"))
      (node (ref "D2") (pin "C") (pinfunction "C_C") (pintype "passive"))
      (node (ref "R12") (pin "1") (pinfunction "1_1") (pintype "passive"))
      (node (ref "R16") (pin "1") (pinfunction "1_1") (pintype "passive"))
      (node (ref "R17") (pin "1") (pinfunction "1_1") (pintype "passive"))
      (node (ref "U2") (pin "11") (pinfunction "17/A5_11") (pintype "bidirectional"))
    )
    (net (code "74") (name "Y_LED") (class "Default")
      (node (ref "LED5") (pin "A") (pinfunction "A_A") (pintype "passive"))
      (node (ref "U2") (pin "27") (pinfunction "MISO/5_27") (pintype "bidirectional"))
    )
    (net (code "75") (name "unconnected-(IC2-DIG4-Pad7)") (class "Default")
      (node (ref "IC2") (pin "7") (pinfunction "DIG4_7") (pintype "bidirectional"))
    )
    (net (code "76") (name "unconnected-(IC3-DIG4-Pad7)") (class "Default")
      (node (ref "IC3") (pin "7") (pinfunction "DIG4_7") (pintype "bidirectional"))
    )
  )
)
